# LWIR_Camera.net
KiCad netlist of a schematic drawn in Altium Designer
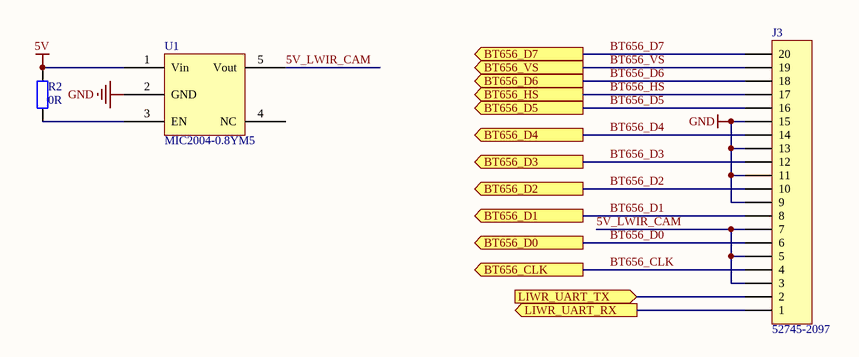
[diagram p0: LWIR_Camera.SchDoc]

(export (version "E")
  (design (tool "Eeschema 10.0.6"))
  (components
    (comp (ref "J3")
      (value "52745-2097")
      (footprint "52745-2097")
      (description "CONN FFC TOP 20POS 0.50MM R/A")
      (fields
        (field (name "MANUFACTURER") "Molex, LLC")
        (field (name "MANUFACTURER PART NUMBER") "0527452097")
      )
      (libsource (lib "KMTI-main") (part "0527452097"))
    )
    (comp (ref "R2")
      (value "0R")
      (footprint "0402R_M")
      (fields (field (name "Comment") "Generic resitor"))
      (libsource (lib "KMTI-main") (part "Resistor"))
    )
    (comp (ref "U1")
      (value "MIC2004-0.8YM5")
      (footprint "SOT23_M5_L")
      (description "IC DISTRIBUTION SW 0.8A SOT23-5")
      (fields (field (name "MANUFACTURER") "Microchip Technology"))
      (libsource (lib "KMTI-main") (part "MIC2004-0.8YM5"))
    )
  )
  (nets
    (net (code "1") (name "/5V_LWIR_CAM") (class "Default")
      (node (ref "J3") (pin "3") (pinfunction "3_3") (pintype "passive"))
      (node (ref "J3") (pin "5") (pinfunction "5_5") (pintype "passive"))
      (node (ref "J3") (pin "7") (pinfunction "7_7") (pintype "passive"))
      (node (ref "U1") (pin "5") (pinfunction "Vout_5") (pintype "passive"))
    )
    (net (code "2") (name "/BT656_CLK") (class "Default")
      (node (ref "J3") (pin "4") (pinfunction "4_4") (pintype "passive"))
    )
    (net (code "3") (name "/BT656_D0") (class "Default")
      (node (ref "J3") (pin "6") (pinfunction "6_6") (pintype "passive"))
    )
    (net (code "4") (name "/BT656_D1") (class "Default")
      (node (ref "J3") (pin "8") (pinfunction "8_8") (pintype "passive"))
    )
    (net (code "5") (name "/BT656_D2") (class "Default")
      (node (ref "J3") (pin "10") (pinfunction "10_10") (pintype "passive"))
    )
    (net (code "6") (name "/BT656_D3") (class "Default")
      (node (ref "J3") (pin "12") (pinfunction "12_12") (pintype "passive"))
    )
    (net (code "7") (name "/BT656_D4") (class "Default")
      (node (ref "J3") (pin "14") (pinfunction "14_14") (pintype "passive"))
    )
    (net (code "8") (name "/BT656_D5") (class "Default")
      (node (ref "J3") (pin "16") (pinfunction "16_16") (pintype "passive"))
    )
    (net (code "9") (name "/BT656_D6") (class "Default")
      (node (ref "J3") (pin "18") (pinfunction "18_18") (pintype "passive"))
    )
    (net (code "10") (name "/BT656_D7") (class "Default")
      (node (ref "J3") (pin "20") (pinfunction "20_20") (pintype "passive"))
    )
    (net (code "11") (name "/BT656_HS") (class "Default")
      (node (ref "J3") (pin "17") (pinfunction "17_17") (pintype "passive"))
    )
    (net (code "12") (name "/BT656_VS") (class "Default")
      (node (ref "J3") (pin "19") (pinfunction "19_19") (pintype "passive"))
    )
    (net (code "13") (name "/LIWR_UART_RX") (class "Default")
      (node (ref "J3") (pin "1") (pinfunction "1_1") (pintype "passive"))
    )
    (net (code "14") (name "/LIWR_UART_TX") (class "Default")
      (node (ref "J3") (pin "2") (pinfunction "2_2") (pintype "passive"))
    )
    (net (code "15") (name "5V") (class "Default")
      (node (ref "R2") (pin "2") (pinfunction "2_2") (pintype "passive"))
      (node (ref "U1") (pin "1") (pinfunction "Vin_1") (pintype "passive"))
    )
    (net (code "16") (name "GND") (class "Default")
      (node (ref "J3") (pin "11") (pinfunction "11_11") (pintype "passive"))
      (node (ref "J3") (pin "13") (pinfunction "13_13") (pintype "passive"))
      (node (ref "J3") (pin "15") (pinfunction "15_15") (pintype "passive"))
      (node (ref "J3") (pin "9") (pinfunction "9_9") (pintype "passive"))
      (node (ref "U1") (pin "2") (pinfunction "GND_2") (pintype "passive"))
    )
    (net (code "17") (name "Net-(U1-EN)") (class "Default")
      (node (ref "R2") (pin "1") (pinfunction "1_1") (pintype "passive"))
      (node (ref "U1") (pin "3") (pinfunction "EN_3") (pintype "passive"))
    )
    (net (code "18") (name "unconnected-(U1-NC-Pad4)") (class "Default")
      (node (ref "U1") (pin "4") (pinfunction "NC_4") (pintype "passive"))
    )
  )
)
